# design.net
KiCad netlist of a schematic drawn in Altium Designer
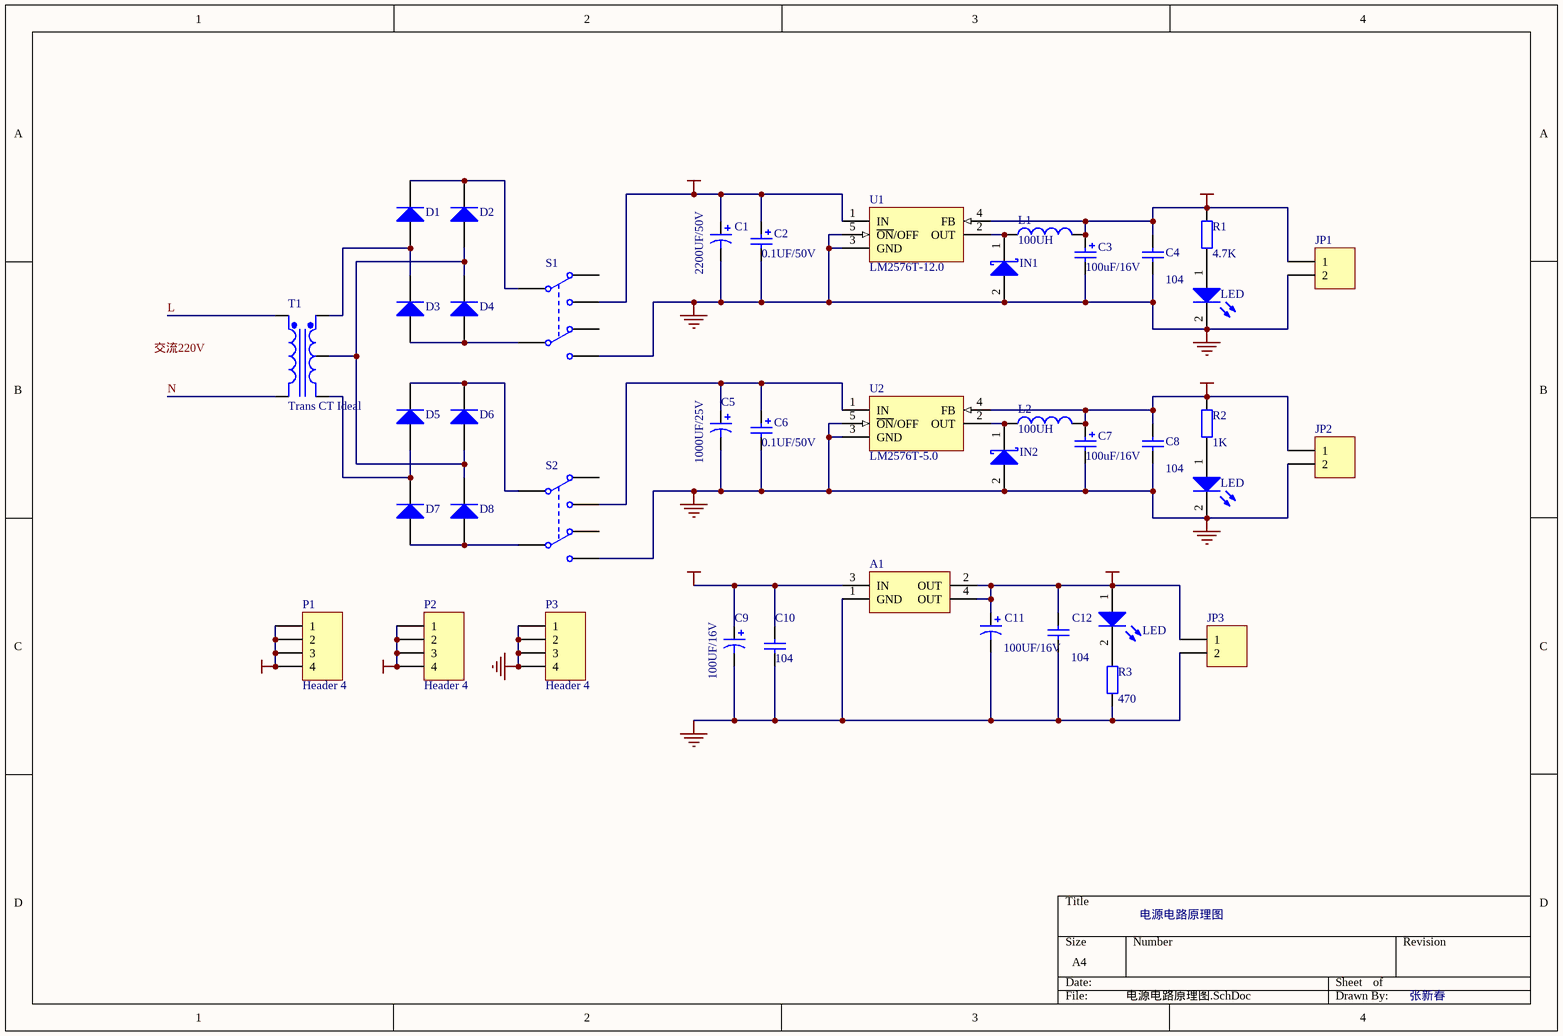
[diagram p0: 电源电路原理图.SchDoc]

(export (version "E")
  (design (tool "Eeschema 10.0.6"))
  (components
    (comp (ref "A1")
      (value "REG1117-3.3")
      (footprint "ZZ311")
      (description "800mA and 1A Low Dropout Positive Regulator 2.85V, 3.3V, 5V, and Adjustable")
      (fields (field (name "PUBLISHER") "Altium Limited"))
      (libsource (lib "BB Power Mgt Voltage Regulator") (part "REG1117-3.3"))
    )
    (comp (ref "C1")
      (value "2200UF/50V")
      (footprint "C-DJ-6")
      (description "Polarized Capacitor (Radial)")
      (fields (field (name "Comment") "Cap Pol1") (field (name "PUBLISHER") "Altium Limited"))
      (libsource (lib "Miscellaneous Devices") (part "Cap Pol1"))
    )
    (comp (ref "C2")
      (value "0.1UF/50V")
      (footprint "C-DJ-6")
      (description "电解电容")
      (fields (field (name "Comment") "DJDR") (field (name "PUBLISHER") "Altium Limited"))
      (libsource (lib "zxcourhc") (part "DJDR"))
    )
    (comp (ref "C3")
      (value "100uF/16V")
      (footprint "C-DJ-6")
      (description "电解电容")
      (fields (field (name "Comment") "DJDR") (field (name "PUBLISHER") "Altium Limited"))
      (libsource (lib "zxcourhc") (part "DJDR"))
    )
    (comp (ref "C4")
      (value "104")
      (footprint "CPDR")
      (description "瓷片电容")
      (fields (field (name "Comment") "CPDR") (field (name "PUBLISHER") "Altium Limited"))
      (libsource (lib "zxcourhc") (part "CPDR"))
    )
    (comp (ref "C5")
      (value "1000UF/25V")
      (footprint "C-DJ-6")
      (description "Polarized Capacitor (Radial)")
      (fields (field (name "Comment") "Cap Pol1") (field (name "PUBLISHER") "Altium Limited"))
      (libsource (lib "Miscellaneous Devices") (part "Cap Pol1"))
    )
    (comp (ref "C6")
      (value "0.1UF/50V")
      (footprint "C-DJ-6")
      (description "电解电容")
      (fields (field (name "Comment") "DJDR") (field (name "PUBLISHER") "Altium Limited"))
      (libsource (lib "zxcourhc") (part "DJDR"))
    )
    (comp (ref "C7")
      (value "100uF/16V")
      (footprint "C-DJ-6")
      (description "电解电容")
      (fields (field (name "Comment") "DJDR") (field (name "PUBLISHER") "Altium Limited"))
      (libsource (lib "zxcourhc") (part "DJDR"))
    )
    (comp (ref "C8")
      (value "104")
      (footprint "CPDR")
      (description "瓷片电容")
      (fields (field (name "Comment") "CPDR") (field (name "PUBLISHER") "Altium Limited"))
      (libsource (lib "zxcourhc") (part "CPDR"))
    )
    (comp (ref "C9")
      (value "100UF/16V")
      (footprint "C-DJ-6")
      (description "Polarized Capacitor (Radial)")
      (fields (field (name "Comment") "Cap Pol1") (field (name "PUBLISHER") "Altium Limited"))
      (libsource (lib "Miscellaneous Devices") (part "Cap Pol1"))
    )
    (comp (ref "C10")
      (value "104")
      (footprint "CPDR")
      (description "Capacitor (Semiconductor SIM Model)")
      (fields (field (name "Comment") "Cap Semi") (field (name "PUBLISHER") "Altium Limited"))
      (libsource (lib "Miscellaneous Devices") (part "Cap Semi"))
    )
    (comp (ref "C11")
      (value "100UF/16V")
      (footprint "C-DJ-4")
      (description "Polarized Capacitor (Radial)")
      (fields (field (name "Comment") "Cap Pol1") (field (name "PUBLISHER") "Altium Limited"))
      (libsource (lib "Miscellaneous Devices") (part "Cap Pol1"))
    )
    (comp (ref "C12")
      (value "104")
      (footprint "CPDR")
      (description "Capacitor (Semiconductor SIM Model)")
      (fields (field (name "Comment") "Cap Semi") (field (name "PUBLISHER") "Altium Limited"))
      (libsource (lib "Miscellaneous Devices") (part "Cap Semi"))
    )
    (comp (ref "D1")
      (value "~")
      (footprint "DIO10.46-5.3x2.8")
      (description "1 Amp General Purpose Rectifier")
      (fields (field (name "PUBLISHER") "Altium Limited"))
      (libsource (lib "Miscellaneous Devices") (part "Diode 1N4007"))
    )
    (comp (ref "D2")
      (value "~")
      (footprint "DIO10.46-5.3x2.8")
      (description "1 Amp General Purpose Rectifier")
      (fields (field (name "PUBLISHER") "Altium Limited"))
      (libsource (lib "Miscellaneous Devices") (part "Diode 1N4007"))
    )
    (comp (ref "D3")
      (value "~")
      (footprint "DIO10.46-5.3x2.8")
      (description "1 Amp General Purpose Rectifier")
      (fields (field (name "PUBLISHER") "Altium Limited"))
      (libsource (lib "Miscellaneous Devices") (part "Diode 1N4007"))
    )
    (comp (ref "D4")
      (value "~")
      (footprint "DIO10.46-5.3x2.8")
      (description "1 Amp General Purpose Rectifier")
      (fields (field (name "PUBLISHER") "Altium Limited"))
      (libsource (lib "Miscellaneous Devices") (part "Diode 1N4007"))
    )
    (comp (ref "D5")
      (value "~")
      (footprint "DIO10.46-5.3x2.8")
      (description "1 Amp General Purpose Rectifier")
      (fields (field (name "PUBLISHER") "Altium Limited"))
      (libsource (lib "Miscellaneous Devices") (part "Diode 1N4007"))
    )
    (comp (ref "D6")
      (value "~")
      (footprint "DIO10.46-5.3x2.8")
      (description "1 Amp General Purpose Rectifier")
      (fields (field (name "PUBLISHER") "Altium Limited"))
      (libsource (lib "Miscellaneous Devices") (part "Diode 1N4007"))
    )
    (comp (ref "D7")
      (value "~")
      (footprint "DIO10.46-5.3x2.8")
      (description "1 Amp General Purpose Rectifier")
      (fields (field (name "PUBLISHER") "Altium Limited"))
      (libsource (lib "Miscellaneous Devices") (part "Diode 1N4007"))
    )
    (comp (ref "D8")
      (value "~")
      (footprint "DIO10.46-5.3x2.8")
      (description "1 Amp General Purpose Rectifier")
      (fields (field (name "PUBLISHER") "Altium Limited"))
      (libsource (lib "Miscellaneous Devices") (part "Diode 1N4007"))
    )
    (comp (ref "DS1")
      (value "LED")
      (footprint "LED_D")
      (description "发光二极管")
      (fields (field (name "PUBLISHER") "Altium Limited"))
      (libsource (lib "zxcourhc") (part "LED"))
    )
    (comp (ref "DS2")
      (value "LED")
      (footprint "LED_D")
      (description "发光二极管")
      (fields (field (name "PUBLISHER") "Altium Limited"))
      (libsource (lib "zxcourhc") (part "LED"))
    )
    (comp (ref "DS3")
      (value "LED")
      (footprint "LED")
      (description "发光二极管")
      (fields (field (name "PUBLISHER") "Altium Limited"))
      (libsource (lib "zxcourhc") (part "LED"))
    )
    (comp (ref "IN1")
      (value "WY2JG")
      (footprint "ZCDZL")
      (description "稳压二级管")
      (fields (field (name "PUBLISHER") "Altium Limited"))
      (libsource (lib "zxcourhc") (part "WY2JG"))
    )
    (comp (ref "IN2")
      (value "WY2JG")
      (footprint "ZCDZL")
      (description "稳压二级管")
      (fields (field (name "PUBLISHER") "Altium Limited"))
      (libsource (lib "zxcourhc") (part "WY2JG"))
    )
    (comp (ref "JP1")
      (value "PZ_2")
      (footprint "JIKEKE")
      (description "排针——2")
      (fields (field (name "PUBLISHER") "Altium Limited"))
      (libsource (lib "zxcourhc") (part "PZ_2"))
    )
    (comp (ref "JP2")
      (value "PZ_2")
      (footprint "JIKEKE")
      (description "排针——2")
      (fields (field (name "PUBLISHER") "Altium Limited"))
      (libsource (lib "zxcourhc") (part "PZ_2"))
    )
    (comp (ref "JP3")
      (value "PZ_2")
      (footprint "JIKEKE")
      (description "排针——2")
      (fields (field (name "PUBLISHER") "Altium Limited"))
      (libsource (lib "zxcourhc") (part "PZ_2"))
    )
    (comp (ref "L1")
      (value "100UH")
      (footprint "L_DG")
      (description "电感")
      (fields (field (name "Comment") "DG") (field (name "PUBLISHER") "Altium Limited"))
      (libsource (lib "zxcourhc") (part "DG"))
    )
    (comp (ref "L2")
      (value "100UH")
      (footprint "L_DG")
      (description "电感")
      (fields (field (name "Comment") "DG") (field (name "PUBLISHER") "Altium Limited"))
      (libsource (lib "zxcourhc") (part "DG"))
    )
    (comp (ref "P1")
      (value "Header 4")
      (footprint "HDR1X4")
      (description "Header, 4-Pin")
      (fields (field (name "PUBLISHER") "Altium Limited"))
      (libsource (lib "Miscellaneous Connectors") (part "Header 4"))
    )
    (comp (ref "P2")
      (value "Header 4")
      (footprint "HDR1X4")
      (description "Header, 4-Pin")
      (fields (field (name "PUBLISHER") "Altium Limited"))
      (libsource (lib "Miscellaneous Connectors") (part "Header 4"))
    )
    (comp (ref "P3")
      (value "Header 4")
      (footprint "HDR1X4")
      (description "Header, 4-Pin")
      (fields (field (name "PUBLISHER") "Altium Limited"))
      (libsource (lib "Miscellaneous Connectors") (part "Header 4"))
    )
    (comp (ref "R1")
      (value "4.7K")
      (footprint "RSE")
      (description "电阻")
      (fields (field (name "Comment") "Res") (field (name "PUBLISHER") "Altium Limited"))
      (libsource (lib "zxcourhc") (part "Res"))
    )
    (comp (ref "R2")
      (value "1K")
      (footprint "RSE")
      (description "电阻")
      (fields (field (name "Comment") "Res") (field (name "PUBLISHER") "Altium Limited"))
      (libsource (lib "zxcourhc") (part "Res"))
    )
    (comp (ref "R3")
      (value "470")
      (footprint "TP-0805-R")
      (description "电阻")
      (fields (field (name "Comment") "Res") (field (name "PUBLISHER") "Altium Limited"))
      (libsource (lib "zxcourhc") (part "Res"))
    )
    (comp (ref "S1")
      (value "~")
      (footprint "DPDT-6")
      (description "Switch")
      (fields (field (name "PUBLISHER") "Altium Limited"))
      (libsource (lib "Miscellaneous Devices") (part "SW DPDT"))
    )
    (comp (ref "S2")
      (value "~")
      (footprint "DPDT-6")
      (description "Switch")
      (fields (field (name "PUBLISHER") "Altium Limited"))
      (libsource (lib "Miscellaneous Devices") (part "SW DPDT"))
    )
    (comp (ref "T1")
      (value "Trans CT Ideal")
      (footprint "T")
      (description "Center-Tapped Transformer (Ideal)")
      (fields (field (name "PUBLISHER") "Altium Limited"))
      (libsource (lib "Miscellaneous Devices") (part "Trans CT Ideal"))
    )
    (comp (ref "U1")
      (value "LM2576T-12.0")
      (footprint "T05A")
      (description "Simple Switcher 3A Step Down Voltage Regulator")
      (fields (field (name "PUBLISHER") "Altium Limited"))
      (libsource (lib "NSC Power Mgt Switching Regulator") (part "LM2576HVT-3.3"))
    )
    (comp (ref "U2")
      (value "LM2576T-5.0")
      (footprint "T05A")
      (description "Simple Switcher 3A Step Down Voltage Regulator")
      (fields (field (name "PUBLISHER") "Altium Limited"))
      (libsource (lib "NSC Power Mgt Switching Regulator") (part "LM2576HVT-3.3"))
    )
  )
  (nets
    (net (code "1") (name "+3.3V") (class "Default")
      (node (ref "A1") (pin "2") (pinfunction "OUT_2") (pintype "power_in"))
      (node (ref "A1") (pin "4") (pinfunction "OUT_4") (pintype "power_in"))
      (node (ref "C11") (pin "1") (pinfunction "1_1") (pintype "passive"))
      (node (ref "C12") (pin "2") (pinfunction "2_2") (pintype "passive"))
      (node (ref "DS3") (pin "1") (pinfunction "A_1") (pintype "passive"))
      (node (ref "JP3") (pin "1") (pinfunction "1_1") (pintype "passive"))
    )
    (net (code "2") (name "+5V") (class "Default")
      (node (ref "A1") (pin "3") (pinfunction "IN_3") (pintype "power_in"))
      (node (ref "C10") (pin "2") (pinfunction "2_2") (pintype "passive"))
      (node (ref "C7") (pin "1") (pinfunction "1_1") (pintype "passive"))
      (node (ref "C8") (pin "2") (pinfunction "2_2") (pintype "passive"))
      (node (ref "C9") (pin "1") (pinfunction "1_1") (pintype "passive"))
      (node (ref "JP2") (pin "1") (pinfunction "1_1") (pintype "passive"))
      (node (ref "L2") (pin "2") (pinfunction "2_2") (pintype "passive"))
      (node (ref "P2") (pin "1") (pinfunction "1_1") (pintype "passive"))
      (node (ref "P2") (pin "2") (pinfunction "2_2") (pintype "passive"))
      (node (ref "P2") (pin "3") (pinfunction "3_3") (pintype "passive"))
      (node (ref "P2") (pin "4") (pinfunction "4_4") (pintype "passive"))
      (node (ref "R2") (pin "2") (pinfunction "2_2") (pintype "passive"))
      (node (ref "U2") (pin "4") (pinfunction "FB_4") (pintype "input"))
    )
    (net (code "3") (name "+12V") (class "Default")
      (node (ref "C3") (pin "1") (pinfunction "1_1") (pintype "passive"))
      (node (ref "C4") (pin "2") (pinfunction "2_2") (pintype "passive"))
      (node (ref "JP1") (pin "1") (pinfunction "1_1") (pintype "passive"))
      (node (ref "L1") (pin "2") (pinfunction "2_2") (pintype "passive"))
      (node (ref "P1") (pin "1") (pinfunction "1_1") (pintype "passive"))
      (node (ref "P1") (pin "2") (pinfunction "2_2") (pintype "passive"))
      (node (ref "P1") (pin "3") (pinfunction "3_3") (pintype "passive"))
      (node (ref "P1") (pin "4") (pinfunction "4_4") (pintype "passive"))
      (node (ref "R1") (pin "2") (pinfunction "2_2") (pintype "passive"))
      (node (ref "U1") (pin "4") (pinfunction "FB_4") (pintype "input"))
    )
    (net (code "4") (name "/L") (class "Default")
      (node (ref "T1") (pin "1") (pinfunction "Pri+_1") (pintype "passive"))
    )
    (net (code "5") (name "/N") (class "Default")
      (node (ref "T1") (pin "2") (pinfunction "Pri-_2") (pintype "passive"))
    )
    (net (code "7") (name "AGND") (class "Default")
      (node (ref "P3") (pin "1") (pinfunction "1_1") (pintype "passive"))
      (node (ref "P3") (pin "2") (pinfunction "2_2") (pintype "passive"))
      (node (ref "P3") (pin "3") (pinfunction "3_3") (pintype "passive"))
      (node (ref "P3") (pin "4") (pinfunction "4_4") (pintype "passive"))
    )
    (net (code "8") (name "GND") (class "Default")
      (node (ref "A1") (pin "1") (pinfunction "GND_1") (pintype "power_in"))
      (node (ref "C1") (pin "2") (pinfunction "2_2") (pintype "passive"))
      (node (ref "C10") (pin "1") (pinfunction "1_1") (pintype "passive"))
      (node (ref "C11") (pin "2") (pinfunction "2_2") (pintype "passive"))
      (node (ref "C12") (pin "1") (pinfunction "1_1") (pintype "passive"))
      (node (ref "C2") (pin "2") (pinfunction "2_2") (pintype "passive"))
      (node (ref "C3") (pin "2") (pinfunction "2_2") (pintype "passive"))
      (node (ref "C4") (pin "1") (pinfunction "1_1") (pintype "passive"))
      (node (ref "C5") (pin "2") (pinfunction "2_2") (pintype "passive"))
      (node (ref "C6") (pin "2") (pinfunction "2_2") (pintype "passive"))
      (node (ref "C7") (pin "2") (pinfunction "2_2") (pintype "passive"))
      (node (ref "C8") (pin "1") (pinfunction "1_1") (pintype "passive"))
      (node (ref "C9") (pin "2") (pinfunction "2_2") (pintype "passive"))
      (node (ref "DS1") (pin "2") (pinfunction "K_2") (pintype "passive"))
      (node (ref "DS2") (pin "2") (pinfunction "K_2") (pintype "passive"))
      (node (ref "IN1") (pin "2") (pinfunction "K_2") (pintype "passive"))
      (node (ref "IN2") (pin "2") (pinfunction "K_2") (pintype "passive"))
      (node (ref "JP1") (pin "2") (pinfunction "2_2") (pintype "passive"))
      (node (ref "JP2") (pin "2") (pinfunction "2_2") (pintype "passive"))
      (node (ref "JP3") (pin "2") (pinfunction "2_2") (pintype "passive"))
      (node (ref "R3") (pin "1") (pinfunction "1_1") (pintype "passive"))
      (node (ref "S1") (pin "6") (pinfunction "NO2_6") (pintype "passive"))
      (node (ref "S2") (pin "6") (pinfunction "NO2_6") (pintype "passive"))
      (node (ref "U1") (pin "3") (pinfunction "GND_3") (pintype "power_in"))
      (node (ref "U1") (pin "5") (pinfunction "~{ON}/OFF_5") (pintype "input"))
      (node (ref "U2") (pin "3") (pinfunction "GND_3") (pintype "power_in"))
      (node (ref "U2") (pin "5") (pinfunction "~{ON}/OFF_5") (pintype "input"))
    )
    (net (code "9") (name "Net-(D1-A)") (class "Default")
      (node (ref "D1") (pin "1") (pinfunction "A_1") (pintype "passive"))
      (node (ref "D3") (pin "2") (pinfunction "K_2") (pintype "passive"))
      (node (ref "T1") (pin "3") (pinfunction "Sec+_3") (pintype "passive"))
    )
    (net (code "10") (name "Net-(D1-K)") (class "Default")
      (node (ref "D1") (pin "2") (pinfunction "K_2") (pintype "passive"))
      (node (ref "D2") (pin "2") (pinfunction "K_2") (pintype "passive"))
      (node (ref "S1") (pin "1") (pinfunction "COMMON1_1") (pintype "passive"))
    )
    (net (code "11") (name "Net-(D2-A)") (class "Default")
      (node (ref "D2") (pin "1") (pinfunction "A_1") (pintype "passive"))
      (node (ref "D4") (pin "2") (pinfunction "K_2") (pintype "passive"))
      (node (ref "D6") (pin "1") (pinfunction "A_1") (pintype "passive"))
      (node (ref "D8") (pin "2") (pinfunction "K_2") (pintype "passive"))
      (node (ref "T1") (pin "4") (pinfunction "SecCT_4") (pintype "passive"))
    )
    (net (code "12") (name "Net-(D3-A)") (class "Default")
      (node (ref "D3") (pin "1") (pinfunction "A_1") (pintype "passive"))
      (node (ref "D4") (pin "1") (pinfunction "A_1") (pintype "passive"))
      (node (ref "S1") (pin "5") (pinfunction "COMMON2_5") (pintype "passive"))
    )
    (net (code "13") (name "Net-(D5-A)") (class "Default")
      (node (ref "D5") (pin "1") (pinfunction "A_1") (pintype "passive"))
      (node (ref "D7") (pin "2") (pinfunction "K_2") (pintype "passive"))
      (node (ref "T1") (pin "5") (pinfunction "Sec-_5") (pintype "passive"))
    )
    (net (code "14") (name "Net-(D5-K)") (class "Default")
      (node (ref "D5") (pin "2") (pinfunction "K_2") (pintype "passive"))
      (node (ref "D6") (pin "2") (pinfunction "K_2") (pintype "passive"))
      (node (ref "S2") (pin "1") (pinfunction "COMMON1_1") (pintype "passive"))
    )
    (net (code "15") (name "Net-(D7-A)") (class "Default")
      (node (ref "D7") (pin "1") (pinfunction "A_1") (pintype "passive"))
      (node (ref "D8") (pin "1") (pinfunction "A_1") (pintype "passive"))
      (node (ref "S2") (pin "5") (pinfunction "COMMON2_5") (pintype "passive"))
    )
    (net (code "16") (name "Net-(DS1-A)") (class "Default")
      (node (ref "DS1") (pin "1") (pinfunction "A_1") (pintype "passive"))
      (node (ref "R1") (pin "1") (pinfunction "1_1") (pintype "passive"))
    )
    (net (code "17") (name "Net-(DS2-A)") (class "Default")
      (node (ref "DS2") (pin "1") (pinfunction "A_1") (pintype "passive"))
      (node (ref "R2") (pin "1") (pinfunction "1_1") (pintype "passive"))
    )
    (net (code "18") (name "Net-(DS3-K)") (class "Default")
      (node (ref "DS3") (pin "2") (pinfunction "K_2") (pintype "passive"))
      (node (ref "R3") (pin "2") (pinfunction "2_2") (pintype "passive"))
    )
    (net (code "19") (name "Net-(IN1-A)") (class "Default")
      (node (ref "IN1") (pin "1") (pinfunction "A_1") (pintype "passive"))
      (node (ref "L1") (pin "1") (pinfunction "1_1") (pintype "passive"))
      (node (ref "U1") (pin "2") (pinfunction "OUT_2") (pintype "power_in"))
    )
    (net (code "20") (name "Net-(IN2-A)") (class "Default")
      (node (ref "IN2") (pin "1") (pinfunction "A_1") (pintype "passive"))
      (node (ref "L2") (pin "1") (pinfunction "1_1") (pintype "passive"))
      (node (ref "U2") (pin "2") (pinfunction "OUT_2") (pintype "power_in"))
    )
    (net (code "21") (name "Net-(S2-NO1)") (class "Default")
      (node (ref "C5") (pin "1") (pinfunction "1_1") (pintype "passive"))
      (node (ref "C6") (pin "1") (pinfunction "1_1") (pintype "passive"))
      (node (ref "S2") (pin "3") (pinfunction "NO1_3") (pintype "passive"))
      (node (ref "U2") (pin "1") (pinfunction "IN_1") (pintype "power_in"))
    )
    (net (code "22") (name "VCC") (class "Default")
      (node (ref "C1") (pin "1") (pinfunction "1_1") (pintype "passive"))
      (node (ref "C2") (pin "1") (pinfunction "1_1") (pintype "passive"))
      (node (ref "S1") (pin "3") (pinfunction "NO1_3") (pintype "passive"))
      (node (ref "U1") (pin "1") (pinfunction "IN_1") (pintype "power_in"))
    )
    (net (code "23") (name "unconnected-(S1-NC1-Pad2)") (class "Default")
      (node (ref "S1") (pin "2") (pinfunction "NC1_2") (pintype "passive"))
    )
    (net (code "24") (name "unconnected-(S1-NC2-Pad4)") (class "Default")
      (node (ref "S1") (pin "4") (pinfunction "NC2_4") (pintype "passive"))
    )
    (net (code "25") (name "unconnected-(S2-NC1-Pad2)") (class "Default")
      (node (ref "S2") (pin "2") (pinfunction "NC1_2") (pintype "passive"))
    )
    (net (code "26") (name "unconnected-(S2-NC2-Pad4)") (class "Default")
      (node (ref "S2") (pin "4") (pinfunction "NC2_4") (pintype "passive"))
    )
  )
)
